# Main_circuit.net
KiCad netlist of a schematic drawn in Altium Designer
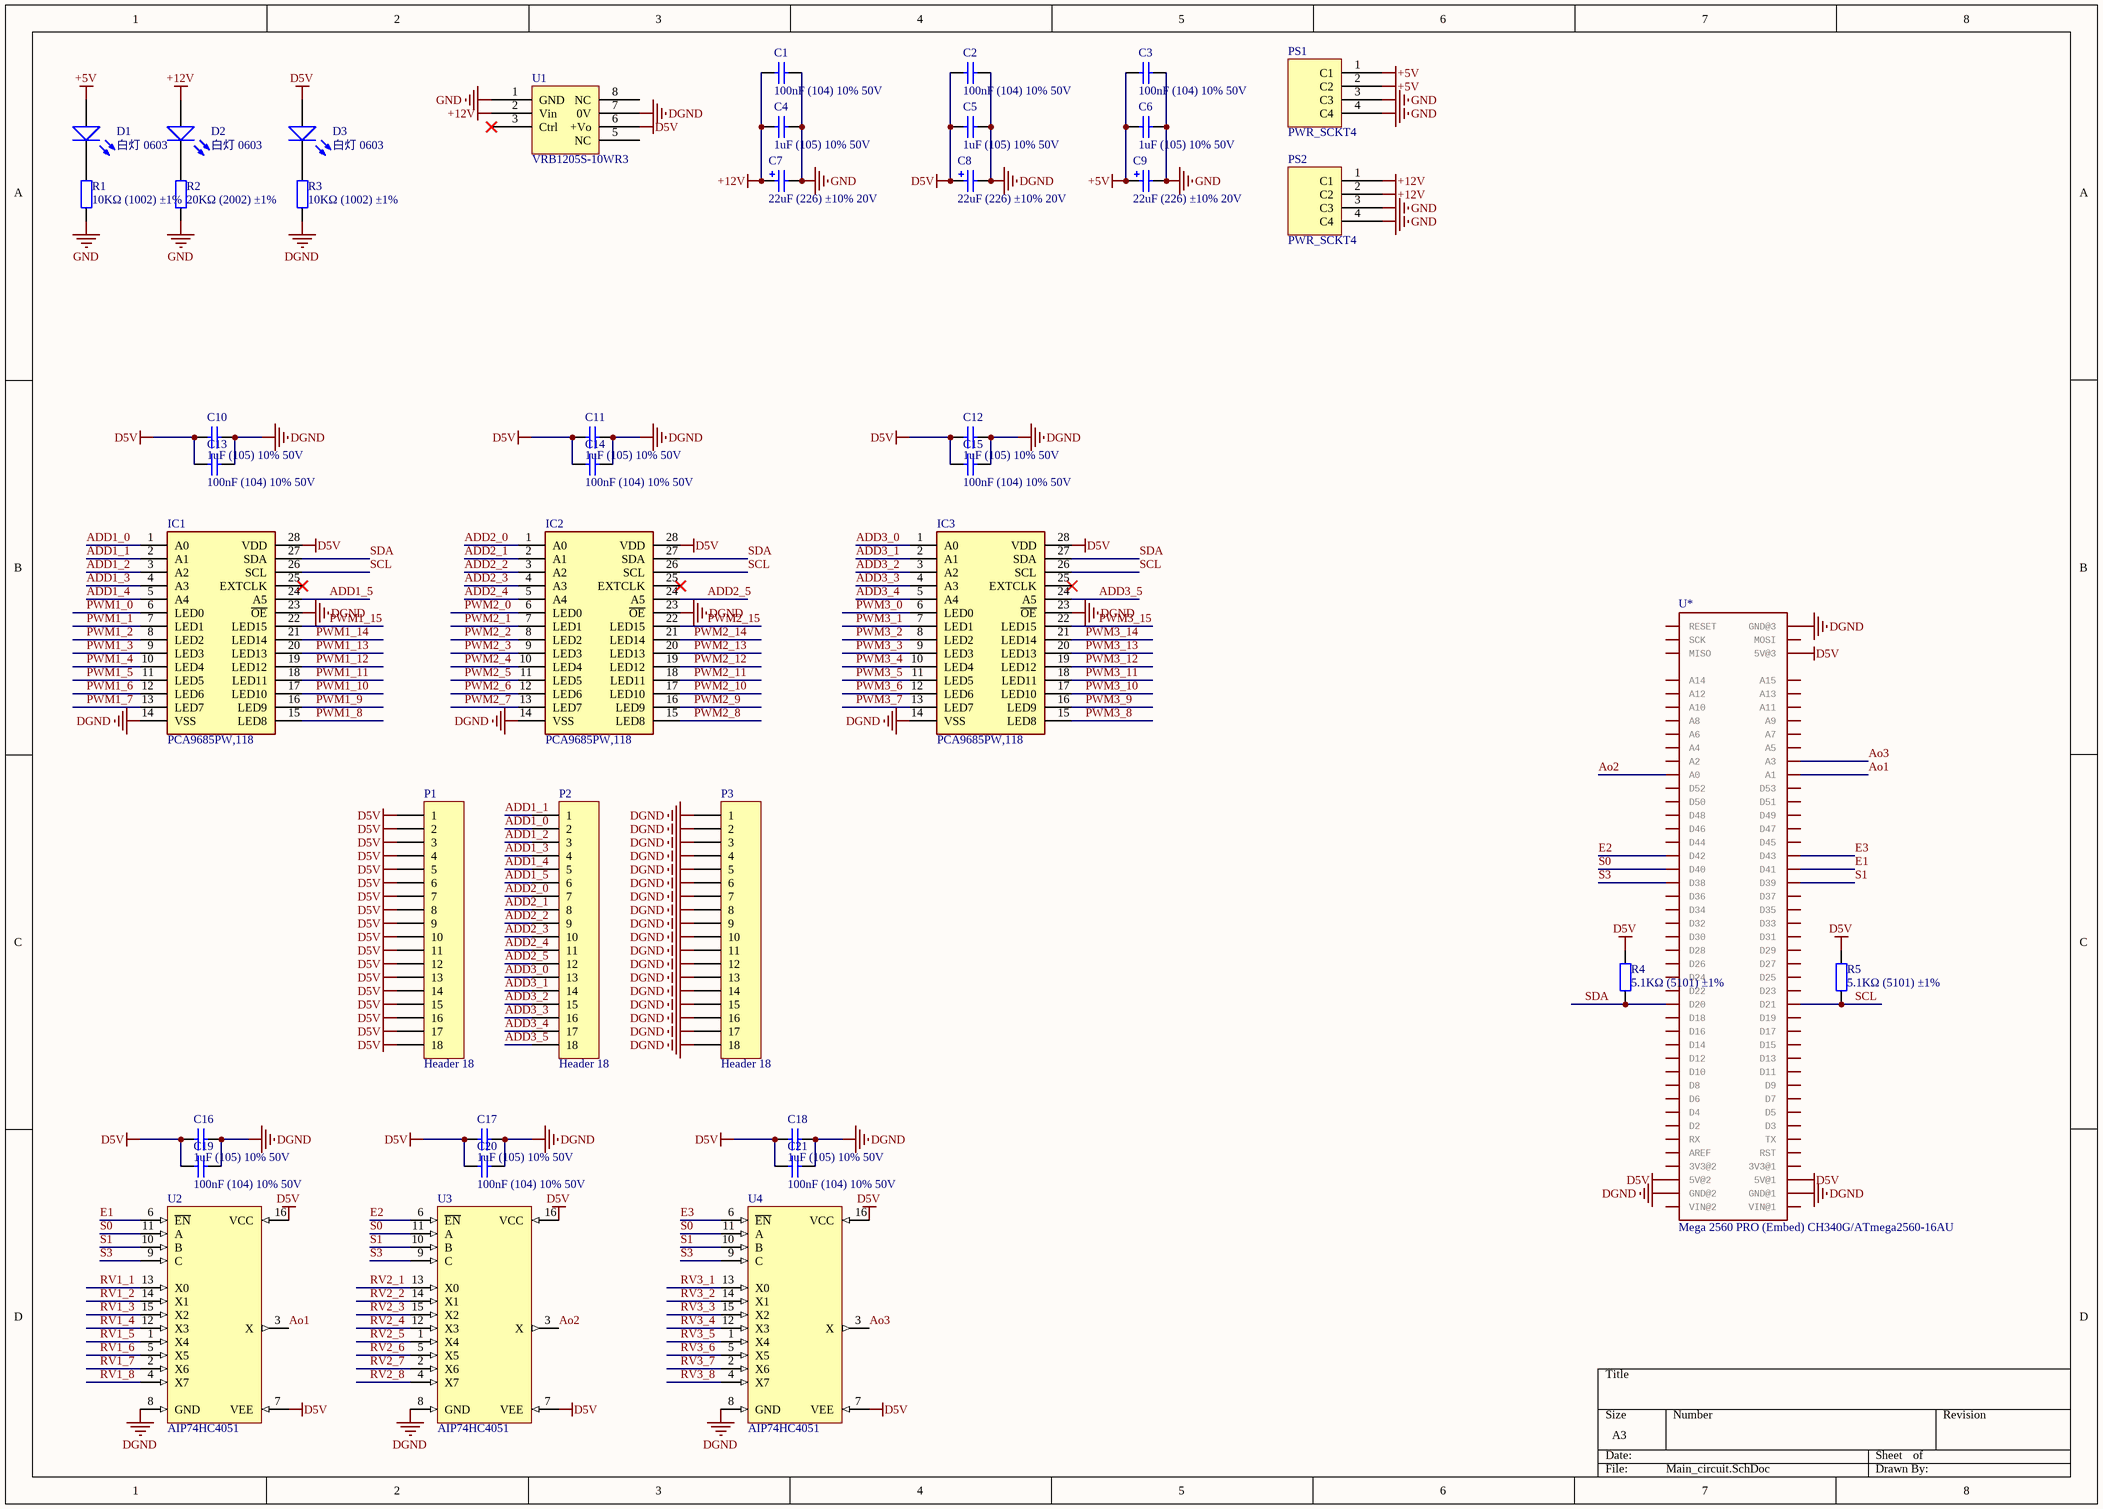
[diagram p0: Main_circuit.SchDoc]

(export (version "E")
  (design (tool "Eeschema 10.0.6"))
  (components
    (comp (ref "C1")
      (value "100nF (104) 10% 50V")
      (footprint "LC-0603_C")
      (description "贴片电容")
      (libsource (lib "Miscellaneous Devices LC") (part "0603 100nF (104) 10% 50V"))
    )
    (comp (ref "C2")
      (value "100nF (104) 10% 50V")
      (footprint "LC-0603_C")
      (description "贴片电容")
      (libsource (lib "Miscellaneous Devices LC") (part "0603 100nF (104) 10% 50V"))
    )
    (comp (ref "C3")
      (value "100nF (104) 10% 50V")
      (footprint "LC-0603_C")
      (description "贴片电容")
      (libsource (lib "Miscellaneous Devices LC") (part "0603 100nF (104) 10% 50V"))
    )
    (comp (ref "C4")
      (value "1uF (105) 10% 50V")
      (footprint "LC-0603_C")
      (description "贴片电容")
      (libsource (lib "Miscellaneous Devices LC") (part "0603 1uF (105) 10% 50V"))
    )
    (comp (ref "C5")
      (value "1uF (105) 10% 50V")
      (footprint "LC-0603_C")
      (description "贴片电容")
      (libsource (lib "Miscellaneous Devices LC") (part "0603 1uF (105) 10% 50V"))
    )
    (comp (ref "C6")
      (value "1uF (105) 10% 50V")
      (footprint "LC-0603_C")
      (description "贴片电容")
      (libsource (lib "Miscellaneous Devices LC") (part "0603 1uF (105) 10% 50V"))
    )
    (comp (ref "C7")
      (value "22uF (226) ±10% 20V")
      (footprint "LC-CASE-B_3528")
      (description "钽电容")
      (libsource (lib "Miscellaneous Devices LC") (part "3216 10uF (106) 10% 16V"))
    )
    (comp (ref "C8")
      (value "22uF (226) ±10% 20V")
      (footprint "LC-CASE-B_3528")
      (description "钽电容")
      (libsource (lib "Miscellaneous Devices LC") (part "3216 10uF (106) 10% 16V"))
    )
    (comp (ref "C9")
      (value "22uF (226) ±10% 20V")
      (footprint "LC-CASE-B_3528")
      (description "钽电容")
      (libsource (lib "Miscellaneous Devices LC") (part "3216 10uF (106) 10% 16V"))
    )
    (comp (ref "C10")
      (value "1uF (105) 10% 50V")
      (footprint "LC-0603_C")
      (description "贴片电容")
      (libsource (lib "Miscellaneous Devices LC") (part "0603 1uF (105) 10% 50V"))
    )
    (comp (ref "C11")
      (value "1uF (105) 10% 50V")
      (footprint "LC-0603_C")
      (description "贴片电容")
      (libsource (lib "Miscellaneous Devices LC") (part "0603 1uF (105) 10% 50V"))
    )
    (comp (ref "C12")
      (value "1uF (105) 10% 50V")
      (footprint "LC-0603_C")
      (description "贴片电容")
      (libsource (lib "Miscellaneous Devices LC") (part "0603 1uF (105) 10% 50V"))
    )
    (comp (ref "C13")
      (value "100nF (104) 10% 50V")
      (footprint "LC-0603_C")
      (description "贴片电容")
      (libsource (lib "Miscellaneous Devices LC") (part "0603 100nF (104) 10% 50V"))
    )
    (comp (ref "C14")
      (value "100nF (104) 10% 50V")
      (footprint "LC-0603_C")
      (description "贴片电容")
      (libsource (lib "Miscellaneous Devices LC") (part "0603 100nF (104) 10% 50V"))
    )
    (comp (ref "C15")
      (value "100nF (104) 10% 50V")
      (footprint "LC-0603_C")
      (description "贴片电容")
      (libsource (lib "Miscellaneous Devices LC") (part "0603 100nF (104) 10% 50V"))
    )
    (comp (ref "C16")
      (value "1uF (105) 10% 50V")
      (footprint "LC-0603_C")
      (description "贴片电容")
      (libsource (lib "Miscellaneous Devices LC") (part "0603 1uF (105) 10% 50V"))
    )
    (comp (ref "C17")
      (value "1uF (105) 10% 50V")
      (footprint "LC-0603_C")
      (description "贴片电容")
      (libsource (lib "Miscellaneous Devices LC") (part "0603 1uF (105) 10% 50V"))
    )
    (comp (ref "C18")
      (value "1uF (105) 10% 50V")
      (footprint "LC-0603_C")
      (description "贴片电容")
      (libsource (lib "Miscellaneous Devices LC") (part "0603 1uF (105) 10% 50V"))
    )
    (comp (ref "C19")
      (value "100nF (104) 10% 50V")
      (footprint "LC-0603_C")
      (description "贴片电容")
      (libsource (lib "Miscellaneous Devices LC") (part "0603 100nF (104) 10% 50V"))
    )
    (comp (ref "C20")
      (value "100nF (104) 10% 50V")
      (footprint "LC-0603_C")
      (description "贴片电容")
      (libsource (lib "Miscellaneous Devices LC") (part "0603 100nF (104) 10% 50V"))
    )
    (comp (ref "C21")
      (value "100nF (104) 10% 50V")
      (footprint "LC-0603_C")
      (description "贴片电容")
      (libsource (lib "Miscellaneous Devices LC") (part "0603 100nF (104) 10% 50V"))
    )
    (comp (ref "D1")
      (value "白灯 0603")
      (footprint "LC-0603_LED_S1")
      (description "发光二极管")
      (libsource (lib "Miscellaneous Devices LC") (part "0603 白灯"))
    )
    (comp (ref "D2")
      (value "白灯 0603")
      (footprint "LC-0603_LED_S1")
      (description "发光二极管")
      (libsource (lib "Miscellaneous Devices LC") (part "0603 白灯"))
    )
    (comp (ref "D3")
      (value "白灯 0603")
      (footprint "LC-0603_LED_S1")
      (description "发光二极管")
      (libsource (lib "Miscellaneous Devices LC") (part "0603 白灯"))
    )
    (comp (ref "IC1")
      (value "PCA9685PW,118")
      (footprint "LC-TSSOP-28")
      (description "Integrated Circuit")
      (libsource (lib "*") (part "PCA9685PW,118"))
    )
    (comp (ref "IC2")
      (value "PCA9685PW,118")
      (footprint "LC-TSSOP-28")
      (description "Integrated Circuit")
      (libsource (lib "*") (part "PCA9685PW,118"))
    )
    (comp (ref "IC3")
      (value "PCA9685PW,118")
      (footprint "LC-TSSOP-28")
      (description "Integrated Circuit")
      (libsource (lib "*") (part "PCA9685PW,118"))
    )
    (comp (ref "P1")
      (value "Header 18")
      (footprint "HDR1X18")
      (description "Header, 18-Pin")
      (fields (field (name "PUBLISHER") "Altium Limited"))
      (libsource (lib "Miscellaneous Connectors") (part "Header 18"))
    )
    (comp (ref "P2")
      (value "Header 18")
      (footprint "HDR1X18")
      (description "Header, 18-Pin")
      (fields (field (name "PUBLISHER") "Altium Limited"))
      (libsource (lib "Miscellaneous Connectors") (part "Header 18"))
    )
    (comp (ref "P3")
      (value "Header 18")
      (footprint "HDR1X18")
      (description "Header, 18-Pin")
      (fields (field (name "PUBLISHER") "Altium Limited"))
      (libsource (lib "Miscellaneous Connectors") (part "Header 18"))
    )
    (comp (ref "PS1")
      (value "PWR_SCKT4")
      (footprint "PWR_SCKT_4P3.81")
      (description "POWER SOCKET")
      (libsource (lib "PG_lib") (part "POWER_SOCKET4"))
    )
    (comp (ref "PS2")
      (value "PWR_SCKT4")
      (footprint "PWR_SCKT_4P3.81")
      (description "POWER SOCKET")
      (libsource (lib "PG_lib") (part "POWER_SOCKET4"))
    )
    (comp (ref "R1")
      (value "10KΩ (1002) ±1%")
      (footprint "LC-0603_R")
      (description "贴片电阻")
      (libsource (lib "Miscellaneous Devices LC") (part "0603 10KΩ (1002) 1%"))
    )
    (comp (ref "R2")
      (value "20KΩ (2002) ±1%")
      (footprint "LC-0603_R")
      (description "贴片电阻")
      (libsource (lib "Miscellaneous Devices LC") (part "0603 20KΩ (2002) 1%"))
    )
    (comp (ref "R3")
      (value "10KΩ (1002) ±1%")
      (footprint "LC-0603_R")
      (description "贴片电阻")
      (libsource (lib "Miscellaneous Devices LC") (part "0603 10KΩ (1002) 1%"))
    )
    (comp (ref "R4")
      (value "5.1KΩ (5101) ±1%")
      (footprint "LC-0603_R")
      (description "贴片电阻")
      (libsource (lib "Miscellaneous Devices LC") (part "0603 5.1KΩ (5101) 1%"))
    )
    (comp (ref "R5")
      (value "5.1KΩ (5101) ±1%")
      (footprint "LC-0603_R")
      (description "贴片电阻")
      (libsource (lib "Miscellaneous Devices LC") (part "0603 5.1KΩ (5101) 1%"))
    )
    (comp (ref "U*")
      (value "Mega 2560 PRO (Embed) CH340G/ATmega2560-16AU")
      (footprint "Mega 2560 PRO (Embed)")
      (libsource (lib "Mega2560Pro") (part "Mega 2560 PRO (Embed)"))
    )
    (comp (ref "U1")
      (value "VRB1205S-10WR3")
      (footprint "VRB1205S-10WR3")
      (libsource (lib "Schlib1") (part "VRB1205S-10WR3"))
    )
    (comp (ref "U2")
      (value "AIP74HC4051")
      (footprint "LC-SOP-16_150mil")
      (description "4000系列逻辑芯片")
      (libsource (lib "Miscellaneous Devices LC") (part "CD4051BM96"))
    )
    (comp (ref "U3")
      (value "AIP74HC4051")
      (footprint "LC-SOP-16_150mil")
      (description "4000系列逻辑芯片")
      (libsource (lib "Miscellaneous Devices LC") (part "CD4051BM96"))
    )
    (comp (ref "U4")
      (value "AIP74HC4051")
      (footprint "LC-SOP-16_150mil")
      (description "4000系列逻辑芯片")
      (libsource (lib "Miscellaneous Devices LC") (part "CD4051BM96"))
    )
  )
  (nets
    (net (code "1") (name "+5V") (class "Default")
      (node (ref "C3") (pin "2") (pinfunction "2_2") (pintype "passive"))
      (node (ref "C6") (pin "2") (pinfunction "2_2") (pintype "passive"))
      (node (ref "C9") (pin "1") (pinfunction "1_1") (pintype "passive"))
      (node (ref "D1") (pin "A") (pinfunction "A_A") (pintype "passive"))
      (node (ref "PS1") (pin "1") (pinfunction "C1_1") (pintype "passive"))
      (node (ref "PS1") (pin "2") (pinfunction "C2_2") (pintype "passive"))
    )
    (net (code "2") (name "+12V") (class "Default")
      (node (ref "C1") (pin "2") (pinfunction "2_2") (pintype "passive"))
      (node (ref "C4") (pin "2") (pinfunction "2_2") (pintype "passive"))
      (node (ref "C7") (pin "1") (pinfunction "1_1") (pintype "passive"))
      (node (ref "D2") (pin "A") (pinfunction "A_A") (pintype "passive"))
      (node (ref "PS2") (pin "1") (pinfunction "C1_1") (pintype "passive"))
      (node (ref "PS2") (pin "2") (pinfunction "C2_2") (pintype "passive"))
      (node (ref "U1") (pin "2") (pinfunction "Vin_2") (pintype "passive"))
    )
    (net (code "3") (name "/ADD1_0") (class "Default")
      (node (ref "IC1") (pin "1") (pinfunction "A0_1") (pintype "passive"))
      (node (ref "P2") (pin "2") (pinfunction "2_2") (pintype "passive"))
    )
    (net (code "4") (name "/ADD1_1") (class "Default")
      (node (ref "IC1") (pin "2") (pinfunction "A1_2") (pintype "passive"))
      (node (ref "P2") (pin "1") (pinfunction "1_1") (pintype "passive"))
    )
    (net (code "5") (name "/ADD1_2") (class "Default")
      (node (ref "IC1") (pin "3") (pinfunction "A2_3") (pintype "passive"))
      (node (ref "P2") (pin "3") (pinfunction "3_3") (pintype "passive"))
    )
    (net (code "6") (name "/ADD1_3") (class "Default")
      (node (ref "IC1") (pin "4") (pinfunction "A3_4") (pintype "passive"))
      (node (ref "P2") (pin "4") (pinfunction "4_4") (pintype "passive"))
    )
    (net (code "7") (name "/ADD1_4") (class "Default")
      (node (ref "IC1") (pin "5") (pinfunction "A4_5") (pintype "passive"))
      (node (ref "P2") (pin "5") (pinfunction "5_5") (pintype "passive"))
    )
    (net (code "8") (name "/ADD1_5") (class "Default")
      (node (ref "IC1") (pin "24") (pinfunction "A5_24") (pintype "passive"))
      (node (ref "P2") (pin "6") (pinfunction "6_6") (pintype "passive"))
    )
    (net (code "9") (name "/ADD2_0") (class "Default")
      (node (ref "IC2") (pin "1") (pinfunction "A0_1") (pintype "passive"))
      (node (ref "P2") (pin "7") (pinfunction "7_7") (pintype "passive"))
    )
    (net (code "10") (name "/ADD2_1") (class "Default")
      (node (ref "IC2") (pin "2") (pinfunction "A1_2") (pintype "passive"))
      (node (ref "P2") (pin "8") (pinfunction "8_8") (pintype "passive"))
    )
    (net (code "11") (name "/ADD2_2") (class "Default")
      (node (ref "IC2") (pin "3") (pinfunction "A2_3") (pintype "passive"))
      (node (ref "P2") (pin "9") (pinfunction "9_9") (pintype "passive"))
    )
    (net (code "12") (name "/ADD2_3") (class "Default")
      (node (ref "IC2") (pin "4") (pinfunction "A3_4") (pintype "passive"))
      (node (ref "P2") (pin "10") (pinfunction "10_10") (pintype "passive"))
    )
    (net (code "13") (name "/ADD2_4") (class "Default")
      (node (ref "IC2") (pin "5") (pinfunction "A4_5") (pintype "passive"))
      (node (ref "P2") (pin "11") (pinfunction "11_11") (pintype "passive"))
    )
    (net (code "14") (name "/ADD2_5") (class "Default")
      (node (ref "IC2") (pin "24") (pinfunction "A5_24") (pintype "passive"))
      (node (ref "P2") (pin "12") (pinfunction "12_12") (pintype "passive"))
    )
    (net (code "15") (name "/ADD3_0") (class "Default")
      (node (ref "IC3") (pin "1") (pinfunction "A0_1") (pintype "passive"))
      (node (ref "P2") (pin "13") (pinfunction "13_13") (pintype "passive"))
    )
    (net (code "16") (name "/ADD3_1") (class "Default")
      (node (ref "IC3") (pin "2") (pinfunction "A1_2") (pintype "passive"))
      (node (ref "P2") (pin "14") (pinfunction "14_14") (pintype "passive"))
    )
    (net (code "17") (name "/ADD3_2") (class "Default")
      (node (ref "IC3") (pin "3") (pinfunction "A2_3") (pintype "passive"))
      (node (ref "P2") (pin "15") (pinfunction "15_15") (pintype "passive"))
    )
    (net (code "18") (name "/ADD3_3") (class "Default")
      (node (ref "IC3") (pin "4") (pinfunction "A3_4") (pintype "passive"))
      (node (ref "P2") (pin "16") (pinfunction "16_16") (pintype "passive"))
    )
    (net (code "19") (name "/ADD3_4") (class "Default")
      (node (ref "IC3") (pin "5") (pinfunction "A4_5") (pintype "passive"))
      (node (ref "P2") (pin "17") (pinfunction "17_17") (pintype "passive"))
    )
    (net (code "20") (name "/ADD3_5") (class "Default")
      (node (ref "IC3") (pin "24") (pinfunction "A5_24") (pintype "passive"))
      (node (ref "P2") (pin "18") (pinfunction "18_18") (pintype "passive"))
    )
    (net (code "21") (name "/Ao1") (class "Default")
      (node (ref "U*") (pin "A1") (pinfunction "A1_A1") (pintype "bidirectional"))
      (node (ref "U2") (pin "3") (pinfunction "X_3") (pintype "output"))
    )
    (net (code "22") (name "/Ao2") (class "Default")
      (node (ref "U*") (pin "A0") (pinfunction "A0_A0") (pintype "bidirectional"))
      (node (ref "U3") (pin "3") (pinfunction "X_3") (pintype "output"))
    )
    (net (code "23") (name "/Ao3") (class "Default")
      (node (ref "U*") (pin "A3") (pinfunction "A3_A3") (pintype "bidirectional"))
      (node (ref "U4") (pin "3") (pinfunction "X_3") (pintype "output"))
    )
    (net (code "24") (name "/E1") (class "Default")
      (node (ref "U*") (pin "D41") (pinfunction "D41_D41") (pintype "bidirectional"))
      (node (ref "U2") (pin "6") (pinfunction "~{EN}_6") (pintype "input"))
    )
    (net (code "25") (name "/E2") (class "Default")
      (node (ref "U*") (pin "D42") (pinfunction "D42_D42") (pintype "bidirectional"))
      (node (ref "U3") (pin "6") (pinfunction "~{EN}_6") (pintype "input"))
    )
    (net (code "26") (name "/E3") (class "Default")
      (node (ref "U*") (pin "D43") (pinfunction "D43_D43") (pintype "bidirectional"))
      (node (ref "U4") (pin "6") (pinfunction "~{EN}_6") (pintype "input"))
    )
    (net (code "27") (name "/PWM1_0") (class "Default")
      (node (ref "IC1") (pin "6") (pinfunction "LED0_6") (pintype "passive"))
    )
    (net (code "28") (name "/PWM1_1") (class "Default")
      (node (ref "IC1") (pin "7") (pinfunction "LED1_7") (pintype "passive"))
    )
    (net (code "29") (name "/PWM1_2") (class "Default")
      (node (ref "IC1") (pin "8") (pinfunction "LED2_8") (pintype "passive"))
    )
    (net (code "30") (name "/PWM1_3") (class "Default")
      (node (ref "IC1") (pin "9") (pinfunction "LED3_9") (pintype "passive"))
    )
    (net (code "31") (name "/PWM1_4") (class "Default")
      (node (ref "IC1") (pin "10") (pinfunction "LED4_10") (pintype "passive"))
    )
    (net (code "32") (name "/PWM1_5") (class "Default")
      (node (ref "IC1") (pin "11") (pinfunction "LED5_11") (pintype "passive"))
    )
    (net (code "33") (name "/PWM1_6") (class "Default")
      (node (ref "IC1") (pin "12") (pinfunction "LED6_12") (pintype "passive"))
    )
    (net (code "34") (name "/PWM1_7") (class "Default")
      (node (ref "IC1") (pin "13") (pinfunction "LED7_13") (pintype "passive"))
    )
    (net (code "35") (name "/PWM1_8") (class "Default")
      (node (ref "IC1") (pin "15") (pinfunction "LED8_15") (pintype "passive"))
    )
    (net (code "36") (name "/PWM1_9") (class "Default")
      (node (ref "IC1") (pin "16") (pinfunction "LED9_16") (pintype "passive"))
    )
    (net (code "37") (name "/PWM1_10") (class "Default")
      (node (ref "IC1") (pin "17") (pinfunction "LED10_17") (pintype "passive"))
    )
    (net (code "38") (name "/PWM1_11") (class "Default")
      (node (ref "IC1") (pin "18") (pinfunction "LED11_18") (pintype "passive"))
    )
    (net (code "39") (name "/PWM1_12") (class "Default")
      (node (ref "IC1") (pin "19") (pinfunction "LED12_19") (pintype "passive"))
    )
    (net (code "40") (name "/PWM1_13") (class "Default")
      (node (ref "IC1") (pin "20") (pinfunction "LED13_20") (pintype "passive"))
    )
    (net (code "41") (name "/PWM1_14") (class "Default")
      (node (ref "IC1") (pin "21") (pinfunction "LED14_21") (pintype "passive"))
    )
    (net (code "42") (name "/PWM1_15") (class "Default")
      (node (ref "IC1") (pin "22") (pinfunction "LED15_22") (pintype "passive"))
    )
    (net (code "43") (name "/PWM2_0") (class "Default")
      (node (ref "IC2") (pin "6") (pinfunction "LED0_6") (pintype "passive"))
    )
    (net (code "44") (name "/PWM2_1") (class "Default")
      (node (ref "IC2") (pin "7") (pinfunction "LED1_7") (pintype "passive"))
    )
    (net (code "45") (name "/PWM2_2") (class "Default")
      (node (ref "IC2") (pin "8") (pinfunction "LED2_8") (pintype "passive"))
    )
    (net (code "46") (name "/PWM2_3") (class "Default")
      (node (ref "IC2") (pin "9") (pinfunction "LED3_9") (pintype "passive"))
    )
    (net (code "47") (name "/PWM2_4") (class "Default")
      (node (ref "IC2") (pin "10") (pinfunction "LED4_10") (pintype "passive"))
    )
    (net (code "48") (name "/PWM2_5") (class "Default")
      (node (ref "IC2") (pin "11") (pinfunction "LED5_11") (pintype "passive"))
    )
    (net (code "49") (name "/PWM2_6") (class "Default")
      (node (ref "IC2") (pin "12") (pinfunction "LED6_12") (pintype "passive"))
    )
    (net (code "50") (name "/PWM2_7") (class "Default")
      (node (ref "IC2") (pin "13") (pinfunction "LED7_13") (pintype "passive"))
    )
    (net (code "51") (name "/PWM2_8") (class "Default")
      (node (ref "IC2") (pin "15") (pinfunction "LED8_15") (pintype "passive"))
    )
    (net (code "52") (name "/PWM2_9") (class "Default")
      (node (ref "IC2") (pin "16") (pinfunction "LED9_16") (pintype "passive"))
    )
    (net (code "53") (name "/PWM2_10") (class "Default")
      (node (ref "IC2") (pin "17") (pinfunction "LED10_17") (pintype "passive"))
    )
    (net (code "54") (name "/PWM2_11") (class "Default")
      (node (ref "IC2") (pin "18") (pinfunction "LED11_18") (pintype "passive"))
    )
    (net (code "55") (name "/PWM2_12") (class "Default")
      (node (ref "IC2") (pin "19") (pinfunction "LED12_19") (pintype "passive"))
    )
    (net (code "56") (name "/PWM2_13") (class "Default")
      (node (ref "IC2") (pin "20") (pinfunction "LED13_20") (pintype "passive"))
    )
    (net (code "57") (name "/PWM2_14") (class "Default")
      (node (ref "IC2") (pin "21") (pinfunction "LED14_21") (pintype "passive"))
    )
    (net (code "58") (name "/PWM2_15") (class "Default")
      (node (ref "IC2") (pin "22") (pinfunction "LED15_22") (pintype "passive"))
    )
    (net (code "59") (name "/PWM3_0") (class "Default")
      (node (ref "IC3") (pin "6") (pinfunction "LED0_6") (pintype "passive"))
    )
    (net (code "60") (name "/PWM3_1") (class "Default")
      (node (ref "IC3") (pin "7") (pinfunction "LED1_7") (pintype "passive"))
    )
    (net (code "61") (name "/PWM3_2") (class "Default")
      (node (ref "IC3") (pin "8") (pinfunction "LED2_8") (pintype "passive"))
    )
    (net (code "62") (name "/PWM3_3") (class "Default")
      (node (ref "IC3") (pin "9") (pinfunction "LED3_9") (pintype "passive"))
    )
    (net (code "63") (name "/PWM3_4") (class "Default")
      (node (ref "IC3") (pin "10") (pinfunction "LED4_10") (pintype "passive"))
    )
    (net (code "64") (name "/PWM3_5") (class "Default")
      (node (ref "IC3") (pin "11") (pinfunction "LED5_11") (pintype "passive"))
    )
    (net (code "65") (name "/PWM3_6") (class "Default")
      (node (ref "IC3") (pin "12") (pinfunction "LED6_12") (pintype "passive"))
    )
    (net (code "66") (name "/PWM3_7") (class "Default")
      (node (ref "IC3") (pin "13") (pinfunction "LED7_13") (pintype "passive"))
    )
    (net (code "67") (name "/PWM3_8") (class "Default")
      (node (ref "IC3") (pin "15") (pinfunction "LED8_15") (pintype "passive"))
    )
    (net (code "68") (name "/PWM3_9") (class "Default")
      (node (ref "IC3") (pin "16") (pinfunction "LED9_16") (pintype "passive"))
    )
    (net (code "69") (name "/PWM3_10") (class "Default")
      (node (ref "IC3") (pin "17") (pinfunction "LED10_17") (pintype "passive"))
    )
    (net (code "70") (name "/PWM3_11") (class "Default")
      (node (ref "IC3") (pin "18") (pinfunction "LED11_18") (pintype "passive"))
    )
    (net (code "71") (name "/PWM3_12") (class "Default")
      (node (ref "IC3") (pin "19") (pinfunction "LED12_19") (pintype "passive"))
    )
    (net (code "72") (name "/PWM3_13") (class "Default")
      (node (ref "IC3") (pin "20") (pinfunction "LED13_20") (pintype "passive"))
    )
    (net (code "73") (name "/PWM3_14") (class "Default")
      (node (ref "IC3") (pin "21") (pinfunction "LED14_21") (pintype "passive"))
    )
    (net (code "74") (name "/PWM3_15") (class "Default")
      (node (ref "IC3") (pin "22") (pinfunction "LED15_22") (pintype "passive"))
    )
    (net (code "75") (name "/RV1_1") (class "Default")
      (node (ref "U2") (pin "13") (pinfunction "X0_13") (pintype "input"))
    )
    (net (code "76") (name "/RV1_2") (class "Default")
      (node (ref "U2") (pin "14") (pinfunction "X1_14") (pintype "input"))
    )
    (net (code "77") (name "/RV1_3") (class "Default")
      (node (ref "U2") (pin "15") (pinfunction "X2_15") (pintype "input"))
    )
    (net (code "78") (name "/RV1_4") (class "Default")
      (node (ref "U2") (pin "12") (pinfunction "X3_12") (pintype "input"))
    )
    (net (code "79") (name "/RV1_5") (class "Default")
      (node (ref "U2") (pin "1") (pinfunction "X4_1") (pintype "input"))
    )
    (net (code "80") (name "/RV1_6") (class "Default")
      (node (ref "U2") (pin "5") (pinfunction "X5_5") (pintype "input"))
    )
    (net (code "81") (name "/RV1_7") (class "Default")
      (node (ref "U2") (pin "2") (pinfunction "X6_2") (pintype "input"))
    )
    (net (code "82") (name "/RV1_8") (class "Default")
      (node (ref "U2") (pin "4") (pinfunction "X7_4") (pintype "input"))
    )
    (net (code "83") (name "/RV2_1") (class "Default")
      (node (ref "U3") (pin "13") (pinfunction "X0_13") (pintype "input"))
    )
    (net (code "84") (name "/RV2_2") (class "Default")
      (node (ref "U3") (pin "14") (pinfunction "X1_14") (pintype "input"))
    )
    (net (code "85") (name "/RV2_3") (class "Default")
      (node (ref "U3") (pin "15") (pinfunction "X2_15") (pintype "input"))
    )
    (net (code "86") (name "/RV2_4") (class "Default")
      (node (ref "U3") (pin "12") (pinfunction "X3_12") (pintype "input"))
    )
    (net (code "87") (name "/RV2_5") (class "Default")
      (node (ref "U3") (pin "1") (pinfunction "X4_1") (pintype "input"))
    )
    (net (code "88") (name "/RV2_6") (class "Default")
      (node (ref "U3") (pin "5") (pinfunction "X5_5") (pintype "input"))
    )
    (net (code "89") (name "/RV2_7") (class "Default")
      (node (ref "U3") (pin "2") (pinfunction "X6_2") (pintype "input"))
    )
    (net (code "90") (name "/RV2_8") (class "Default")
      (node (ref "U3") (pin "4") (pinfunction "X7_4") (pintype "input"))
    )
    (net (code "91") (name "/RV3_1") (class "Default")
      (node (ref "U4") (pin "13") (pinfunction "X0_13") (pintype "input"))
    )
    (net (code "92") (name "/RV3_2") (class "Default")
      (node (ref "U4") (pin "14") (pinfunction "X1_14") (pintype "input"))
    )
    (net (code "93") (name "/RV3_3") (class "Default")
      (node (ref "U4") (pin "15") (pinfunction "X2_15") (pintype "input"))
    )
    (net (code "94") (name "/RV3_4") (class "Default")
      (node (ref "U4") (pin "12") (pinfunction "X3_12") (pintype "input"))
    )
    (net (code "95") (name "/RV3_5") (class "Default")
      (node (ref "U4") (pin "1") (pinfunction "X4_1") (pintype "input"))
    )
    (net (code "96") (name "/RV3_6") (class "Default")
      (node (ref "U4") (pin "5") (pinfunction "X5_5") (pintype "input"))
    )
    (net (code "97") (name "/RV3_7") (class "Default")
      (node (ref "U4") (pin "2") (pinfunction "X6_2") (pintype "input"))
    )
    (net (code "98") (name "/RV3_8") (class "Default")
      (node (ref "U4") (pin "4") (pinfunction "X7_4") (pintype "input"))
    )
    (net (code "99") (name "/S0") (class "Default")
      (node (ref "U*") (pin "D40") (pinfunction "D40_D40") (pintype "bidirectional"))
      (node (ref "U2") (pin "11") (pinfunction "A_11") (pintype "input"))
      (node (ref "U3") (pin "11") (pinfunction "A_11") (pintype "input"))
      (node (ref "U4") (pin "11") (pinfunction "A_11") (pintype "input"))
    )
    (net (code "100") (name "/S1") (class "Default")
      (node (ref "U*") (pin "D39") (pinfunction "D39_D39") (pintype "bidirectional"))
      (node (ref "U2") (pin "10") (pinfunction "B_10") (pintype "input"))
      (node (ref "U3") (pin "10") (pinfunction "B_10") (pintype "input"))
      (node (ref "U4") (pin "10") (pinfunction "B_10") (pintype "input"))
    )
    (net (code "101") (name "/S3") (class "Default")
      (node (ref "U*") (pin "D38") (pinfunction "D38_D38") (pintype "bidirectional"))
      (node (ref "U2") (pin "9") (pinfunction "C_9") (pintype "input"))
      (node (ref "U3") (pin "9") (pinfunction "C_9") (pintype "input"))
      (node (ref "U4") (pin "9") (pinfunction "C_9") (pintype "input"))
    )
    (net (code "102") (name "/SCL") (class "Default")
      (node (ref "IC1") (pin "26") (pinfunction "SCL_26") (pintype "passive"))
      (node (ref "IC2") (pin "26") (pinfunction "SCL_26") (pintype "passive"))
      (node (ref "IC3") (pin "26") (pinfunction "SCL_26") (pintype "passive"))
      (node (ref "R5") (pin "1") (pinfunction "1_1") (pintype "passive"))
      (node (ref "U*") (pin "D21") (pinfunction "D21_D21") (pintype "bidirectional"))
    )
    (net (code "103") (name "/SDA") (class "Default")
      (node (ref "IC1") (pin "27") (pinfunction "SDA_27") (pintype "passive"))
      (node (ref "IC2") (pin "27") (pinfunction "SDA_27") (pintype "passive"))
      (node (ref "IC3") (pin "27") (pinfunction "SDA_27") (pintype "passive"))
      (node (ref "R4") (pin "1") (pinfunction "1_1") (pintype "passive"))
      (node (ref "U*") (pin "D20") (pinfunction "D20_D20") (pintype "bidirectional"))
    )
    (net (code "104") (name "D5V") (class "Default")
      (node (ref "C10") (pin "1") (pinfunction "1_1") (pintype "passive"))
      (node (ref "C11") (pin "1") (pinfunction "1_1") (pintype "passive"))
      (node (ref "C12") (pin "1") (pinfunction "1_1") (pintype "passive"))
      (node (ref "C13") (pin "1") (pinfunction "1_1") (pintype "passive"))
      (node (ref "C14") (pin "1") (pinfunction "1_1") (pintype "passive"))
      (node (ref "C15") (pin "1") (pinfunction "1_1") (pintype "passive"))
      (node (ref "C16") (pin "1") (pinfunction "1_1") (pintype "passive"))
      (node (ref "C17") (pin "1") (pinfunction "1_1") (pintype "passive"))
      (node (ref "C18") (pin "1") (pinfunction "1_1") (pintype "passive"))
      (node (ref "C19") (pin "1") (pinfunction "1_1") (pintype "passive"))
      (node (ref "C2") (pin "2") (pinfunction "2_2") (pintype "passive"))
      (node (ref "C20") (pin "1") (pinfunction "1_1") (pintype "passive"))
      (node (ref "C21") (pin "1") (pinfunction "1_1") (pintype "passive"))
      (node (ref "C5") (pin "2") (pinfunction "2_2") (pintype "passive"))
      (node (ref "C8") (pin "1") (pinfunction "1_1") (pintype "passive"))
      (node (ref "D3") (pin "A") (pinfunction "A_A") (pintype "passive"))
      (node (ref "IC1") (pin "28") (pinfunction "VDD_28") (pintype "passive"))
      (node (ref "IC2") (pin "28") (pinfunction "VDD_28") (pintype "passive"))
      (node (ref "IC3") (pin "28") (pinfunction "VDD_28") (pintype "passive"))
      (node (ref "P1") (pin "1") (pinfunction "1_1") (pintype "passive"))
      (node (ref "P1") (pin "10") (pinfunction "10_10") (pintype "passive"))
      (node (ref "P1") (pin "11") (pinfunction "11_11") (pintype "passive"))
      (node (ref "P1") (pin "12") (pinfunction "12_12") (pintype "passive"))
      (node (ref "P1") (pin "13") (pinfunction "13_13") (pintype "passive"))
      (node (ref "P1") (pin "14") (pinfunction "14_14") (pintype "passive"))
      (node (ref "P1") (pin "15") (pinfunction "15_15") (pintype "passive"))
      (node (ref "P1") (pin "16") (pinfunction "16_16") (pintype "passive"))
      (node (ref "P1") (pin "17") (pinfunction "17_17") (pintype "passive"))
      (node (ref "P1") (pin "18") (pinfunction "18_18") (pintype "passive"))
      (node (ref "P1") (pin "2") (pinfunction "2_2") (pintype "passive"))
      (node (ref "P1") (pin "3") (pinfunction "3_3") (pintype "passive"))
      (node (ref "P1") (pin "4") (pinfunction "4_4") (pintype "passive"))
      (node (ref "P1") (pin "5") (pinfunction "5_5") (pintype "passive"))
      (node (ref "P1") (pin "6") (pinfunction "6_6") (pintype "passive"))
      (node (ref "P1") (pin "7") (pinfunction "7_7") (pintype "passive"))
      (node (ref "P1") (pin "8") (pinfunction "8_8") (pintype "passive"))
      (node (ref "P1") (pin "9") (pinfunction "9_9") (pintype "passive"))
      (node (ref "R4") (pin "2") (pinfunction "2_2") (pintype "passive"))
      (node (ref "R5") (pin "2") (pinfunction "2_2") (pintype "passive"))
      (node (ref "U*") (pin "5V@1") (pinfunction "5V@1_5V@1") (pintype "bidirectional"))
      (node (ref "U*") (pin "5V@2") (pinfunction "5V@2_5V@2") (pintype "bidirectional"))
      (node (ref "U*") (pin "5V@3") (pinfunction "5V@3_5V@3") (pintype "bidirectional"))
      (node (ref "U1") (pin "6") (pinfunction "+Vo_6") (pintype "passive"))
      (node (ref "U2") (pin "16") (pinfunction "VCC_16") (pintype "input"))
      (node (ref "U2") (pin "7") (pinfunction "VEE_7") (pintype "input"))
      (node (ref "U3") (pin "16") (pinfunction "VCC_16") (pintype "input"))
      (node (ref "U3") (pin "7") (pinfunction "VEE_7") (pintype "input"))
      (node (ref "U4") (pin "16") (pinfunction "VCC_16") (pintype "input"))
      (node (ref "U4") (pin "7") (pinfunction "VEE_7") (pintype "input"))
    )
    (net (code "105") (name "DGND") (class "Default")
      (node (ref "C10") (pin "2") (pinfunction "2_2") (pintype "passive"))
      (node (ref "C11") (pin "2") (pinfunction "2_2") (pintype "passive"))
      (node (ref "C12") (pin "2") (pinfunction "2_2") (pintype "passive"))
      (node (ref "C13") (pin "2") (pinfunction "2_2") (pintype "passive"))
      (node (ref "C14") (pin "2") (pinfunction "2_2") (pintype "passive"))
      (node (ref "C15") (pin "2") (pinfunction "2_2") (pintype "passive"))
      (node (ref "C16") (pin "2") (pinfunction "2_2") (pintype "passive"))
      (node (ref "C17") (pin "2") (pinfunction "2_2") (pintype "passive"))
      (node (ref "C18") (pin "2") (pinfunction "2_2") (pintype "passive"))
      (node (ref "C19") (pin "2") (pinfunction "2_2") (pintype "passive"))
      (node (ref "C2") (pin "1") (pinfunction "1_1") (pintype "passive"))
      (node (ref "C20") (pin "2") (pinfunction "2_2") (pintype "passive"))
      (node (ref "C21") (pin "2") (pinfunction "2_2") (pintype "passive"))
      (node (ref "C5") (pin "1") (pinfunction "1_1") (pintype "passive"))
      (node (ref "C8") (pin "2") (pinfunction "2_2") (pintype "passive"))
      (node (ref "IC1") (pin "14") (pinfunction "VSS_14") (pintype "passive"))
      (node (ref "IC1") (pin "23") (pinfunction "~{OE}_23") (pintype "passive"))
      (node (ref "IC2") (pin "14") (pinfunction "VSS_14") (pintype "passive"))
      (node (ref "IC2") (pin "23") (pinfunction "~{OE}_23") (pintype "passive"))
      (node (ref "IC3") (pin "14") (pinfunction "VSS_14") (pintype "passive"))
      (node (ref "IC3") (pin "23") (pinfunction "~{OE}_23") (pintype "passive"))
      (node (ref "P3") (pin "1") (pinfunction "1_1") (pintype "passive"))
      (node (ref "P3") (pin "10") (pinfunction "10_10") (pintype "passive"))
      (node (ref "P3") (pin "11") (pinfunction "11_11") (pintype "passive"))
      (node (ref "P3") (pin "12") (pinfunction "12_12") (pintype "passive"))
      (node (ref "P3") (pin "13") (pinfunction "13_13") (pintype "passive"))
      (node (ref "P3") (pin "14") (pinfunction "14_14") (pintype "passive"))
      (node (ref "P3") (pin "15") (pinfunction "15_15") (pintype "passive"))
      (node (ref "P3") (pin "16") (pinfunction "16_16") (pintype "passive"))
      (node (ref "P3") (pin "17") (pinfunction "17_17") (pintype "passive"))
      (node (ref "P3") (pin "18") (pinfunction "18_18") (pintype "passive"))
      (node (ref "P3") (pin "2") (pinfunction "2_2") (pintype "passive"))
      (node (ref "P3") (pin "3") (pinfunction "3_3") (pintype "passive"))
      (node (ref "P3") (pin "4") (pinfunction "4_4") (pintype "passive"))
      (node (ref "P3") (pin "5") (pinfunction "5_5") (pintype "passive"))
      (node (ref "P3") (pin "6") (pinfunction "6_6") (pintype "passive"))
      (node (ref "P3") (pin "7") (pinfunction "7_7") (pintype "passive"))
      (node (ref "P3") (pin "8") (pinfunction "8_8") (pintype "passive"))
      (node (ref "P3") (pin "9") (pinfunction "9_9") (pintype "passive"))
      (node (ref "R3") (pin "1") (pinfunction "1_1") (pintype "passive"))
      (node (ref "U*") (pin "GND@1") (pinfunction "GND@1_GND@1") (pintype "bidirectional"))
      (node (ref "U*") (pin "GND@2") (pinfunction "GND@2_GND@2") (pintype "bidirectional"))
      (node (ref "U*") (pin "GND@3") (pinfunction "GND@3_GND@3") (pintype "bidirectional"))
      (node (ref "U1") (pin "7") (pinfunction "0V_7") (pintype "passive"))
      (node (ref "U2") (pin "8") (pinfunction "GND_8") (pintype "input"))
      (node (ref "U3") (pin "8") (pinfunction "GND_8") (pintype "input"))
      (node (ref "U4") (pin "8") (pinfunction "GND_8") (pintype "input"))
    )
    (net (code "106") (name "GND") (class "Default")
      (node (ref "C1") (pin "1") (pinfunction "1_1") (pintype "passive"))
      (node (ref "C3") (pin "1") (pinfunction "1_1") (pintype "passive"))
      (node (ref "C4") (pin "1") (pinfunction "1_1") (pintype "passive"))
      (node (ref "C6") (pin "1") (pinfunction "1_1") (pintype "passive"))
      (node (ref "C7") (pin "2") (pinfunction "2_2") (pintype "passive"))
      (node (ref "C9") (pin "2") (pinfunction "2_2") (pintype "passive"))
      (node (ref "PS1") (pin "3") (pinfunction "C3_3") (pintype "passive"))
      (node (ref "PS1") (pin "4") (pinfunction "C4_4") (pintype "passive"))
      (node (ref "PS2") (pin "3") (pinfunction "C3_3") (pintype "passive"))
      (node (ref "PS2") (pin "4") (pinfunction "C4_4") (pintype "passive"))
      (node (ref "R1") (pin "1") (pinfunction "1_1") (pintype "passive"))
      (node (ref "R2") (pin "1") (pinfunction "1_1") (pintype "passive"))
      (node (ref "U1") (pin "1") (pinfunction "GND_1") (pintype "passive"))
    )
    (net (code "107") (name "Net-(D1-PadK)") (class "Default")
      (node (ref "D1") (pin "K") (pinfunction "K_K") (pintype "passive"))
      (node (ref "R1") (pin "2") (pinfunction "2_2") (pintype "passive"))
    )
    (net (code "108") (name "Net-(D2-PadK)") (class "Default")
      (node (ref "D2") (pin "K") (pinfunction "K_K") (pintype "passive"))
      (node (ref "R2") (pin "2") (pinfunction "2_2") (pintype "passive"))
    )
    (net (code "109") (name "Net-(D3-PadK)") (class "Default")
      (node (ref "D3") (pin "K") (pinfunction "K_K") (pintype "passive"))
      (node (ref "R3") (pin "2") (pinfunction "2_2") (pintype "passive"))
    )
    (net (code "110") (name "unconnected-(IC1-EXTCLK-Pad25)") (class "Default")
      (node (ref "IC1") (pin "25") (pinfunction "EXTCLK_25") (pintype "passive+no_connect"))
    )
    (net (code "111") (name "unconnected-(IC2-EXTCLK-Pad25)") (class "Default")
      (node (ref "IC2") (pin "25") (pinfunction "EXTCLK_25") (pintype "passive+no_connect"))
    )
    (net (code "112") (name "unconnected-(IC3-EXTCLK-Pad25)") (class "Default")
      (node (ref "IC3") (pin "25") (pinfunction "EXTCLK_25") (pintype "passive+no_connect"))
    )
    (net (code "113") (name "unconnected-(U*-Pad3V3@1)") (class "Default")
      (node (ref "U*") (pin "3V3@1") (pinfunction "3V3@1_3V3@1") (pintype "bidirectional"))
    )
    (net (code "114") (name "unconnected-(U*-Pad3V3@2)") (class "Default")
      (node (ref "U*") (pin "3V3@2") (pinfunction "3V3@2_3V3@2") (pintype "bidirectional"))
    )
    (net (code "115") (name "unconnected-(U*-PadA2)") (class "Default")
      (node (ref "U*") (pin "A2") (pinfunction "A2_A2") (pintype "bidirectional"))
    )
    (net (code "116") (name "unconnected-(U*-PadA4)") (class "Default")
      (node (ref "U*") (pin "A4") (pinfunction "A4_A4") (pintype "bidirectional"))
    )
    (net (code "117") (name "unconnected-(U*-PadA5)") (class "Default")
      (node (ref "U*") (pin "A5") (pinfunction "A5_A5") (pintype "bidirectional"))
    )
    (net (code "118") (name "unconnected-(U*-PadA6)") (class "Default")
      (node (ref "U*") (pin "A6") (pinfunction "A6_A6") (pintype "bidirectional"))
    )
    (net (code "119") (name "unconnected-(U*-PadA7)") (class "Default")
      (node (ref "U*") (pin "A7") (pinfunction "A7_A7") (pintype "bidirectional"))
    )
    (net (code "120") (name "unconnected-(U*-PadA8)") (class "Default")
      (node (ref "U*") (pin "A8") (pinfunction "A8_A8") (pintype "bidirectional"))
    )
    (net (code "121") (name "unconnected-(U*-PadA9)") (class "Default")
      (node (ref "U*") (pin "A9") (pinfunction "A9_A9") (pintype "bidirectional"))
    )
    (net (code "122") (name "unconnected-(U*-PadA10)") (class "Default")
      (node (ref "U*") (pin "A10") (pinfunction "A10_A10") (pintype "bidirectional"))
    )
    (net (code "123") (name "unconnected-(U*-PadA11)") (class "Default")
      (node (ref "U*") (pin "A11") (pinfunction "A11_A11") (pintype "bidirectional"))
    )
    (net (code "124") (name "unconnected-(U*-PadA12)") (class "Default")
      (node (ref "U*") (pin "A12") (pinfunction "A12_A12") (pintype "bidirectional"))
    )
    (net (code "125") (name "unconnected-(U*-PadA13)") (class "Default")
      (node (ref "U*") (pin "A13") (pinfunction "A13_A13") (pintype "bidirectional"))
    )
    (net (code "126") (name "unconnected-(U*-PadA14)") (class "Default")
      (node (ref "U*") (pin "A14") (pinfunction "A14_A14") (pintype "bidirectional"))
    )
    (net (code "127") (name "unconnected-(U*-PadA15)") (class "Default")
      (node (ref "U*") (pin "A15") (pinfunction "A15_A15") (pintype "bidirectional"))
    )
    (net (code "128") (name "unconnected-(U*-PadAREF)") (class "Default")
      (node (ref "U*") (pin "AREF") (pinfunction "AREF_AREF") (pintype "bidirectional"))
    )
    (net (code "129") (name "unconnected-(U*-PadD2)") (class "Default")
      (node (ref "U*") (pin "D2") (pinfunction "D2_D2") (pintype "bidirectional"))
    )
    (net (code "130") (name "unconnected-(U*-PadD3)") (class "Default")
      (node (ref "U*") (pin "D3") (pinfunction "D3_D3") (pintype "bidirectional"))
    )
    (net (code "131") (name "unconnected-(U*-PadD4)") (class "Default")
      (node (ref "U*") (pin "D4") (pinfunction "D4_D4") (pintype "bidirectional"))
    )
    (net (code "132") (name "unconnected-(U*-PadD5)") (class "Default")
      (node (ref "U*") (pin "D5") (pinfunction "D5_D5") (pintype "bidirectional"))
    )
    (net (code "133") (name "unconnected-(U*-PadD6)") (class "Default")
      (node (ref "U*") (pin "D6") (pinfunction "D6_D6") (pintype "bidirectional"))
    )
    (net (code "134") (name "unconnected-(U*-PadD7)") (class "Default")
      (node (ref "U*") (pin "D7") (pinfunction "D7_D7") (pintype "bidirectional"))
    )
    (net (code "135") (name "unconnected-(U*-PadD8)") (class "Default")
      (node (ref "U*") (pin "D8") (pinfunction "D8_D8") (pintype "bidirectional"))
    )
    (net (code "136") (name "unconnected-(U*-PadD9)") (class "Default")
      (node (ref "U*") (pin "D9") (pinfunction "D9_D9") (pintype "bidirectional"))
    )
    (net (code "137") (name "unconnected-(U*-PadD10)") (class "Default")
      (node (ref "U*") (pin "D10") (pinfunction "D10_D10") (pintype "bidirectional"))
    )
    (net (code "138") (name "unconnected-(U*-PadD11)") (class "Default")
      (node (ref "U*") (pin "D11") (pinfunction "D11_D11") (pintype "bidirectional"))
    )
    (net (code "139") (name "unconnected-(U*-PadD12)") (class "Default")
      (node (ref "U*") (pin "D12") (pinfunction "D12_D12") (pintype "bidirectional"))
    )
    (net (code "140") (name "unconnected-(U*-PadD13)") (class "Default")
      (node (ref "U*") (pin "D13") (pinfunction "D13_D13") (pintype "bidirectional"))
    )
    (net (code "141") (name "unconnected-(U*-PadD14)") (class "Default")
      (node (ref "U*") (pin "D14") (pinfunction "D14_D14") (pintype "bidirectional"))
    )
    (net (code "142") (name "unconnected-(U*-PadD15)") (class "Default")
      (node (ref "U*") (pin "D15") (pinfunction "D15_D15") (pintype "bidirectional"))
    )
    (net (code "143") (name "unconnected-(U*-PadD16)") (class "Default")
      (node (ref "U*") (pin "D16") (pinfunction "D16_D16") (pintype "bidirectional"))
    )
    (net (code "144") (name "unconnected-(U*-PadD17)") (class "Default")
      (node (ref "U*") (pin "D17") (pinfunction "D17_D17") (pintype "bidirectional"))
    )
    (net (code "145") (name "unconnected-(U*-PadD18)") (class "Default")
      (node (ref "U*") (pin "D18") (pinfunction "D18_D18") (pintype "bidirectional"))
    )
    (net (code "146") (name "unconnected-(U*-PadD19)") (class "Default")
      (node (ref "U*") (pin "D19") (pinfunction "D19_D19") (pintype "bidirectional"))
    )
    (net (code "147") (name "unconnected-(U*-PadD22)") (class "Default")
      (node (ref "U*") (pin "D22") (pinfunction "D22_D22") (pintype "bidirectional"))
    )
    (net (code "148") (name "unconnected-(U*-PadD23)") (class "Default")
      (node (ref "U*") (pin "D23") (pinfunction "D23_D23") (pintype "bidirectional"))
    )
    (net (code "149") (name "unconnected-(U*-PadD24)") (class "Default")
      (node (ref "U*") (pin "D24") (pinfunction "D24_D24") (pintype "bidirectional"))
    )
    (net (code "150") (name "unconnected-(U*-PadD25)") (class "Default")
      (node (ref "U*") (pin "D25") (pinfunction "D25_D25") (pintype "bidirectional"))
    )
    (net (code "151") (name "unconnected-(U*-PadD26)") (class "Default")
      (node (ref "U*") (pin "D26") (pinfunction "D26_D26") (pintype "bidirectional"))
    )
    (net (code "152") (name "unconnected-(U*-PadD27)") (class "Default")
      (node (ref "U*") (pin "D27") (pinfunction "D27_D27") (pintype "bidirectional"))
    )
    (net (code "153") (name "unconnected-(U*-PadD28)") (class "Default")
      (node (ref "U*") (pin "D28") (pinfunction "D28_D28") (pintype "bidirectional"))
    )
    (net (code "154") (name "unconnected-(U*-PadD29)") (class "Default")
      (node (ref "U*") (pin "D29") (pinfunction "D29_D29") (pintype "bidirectional"))
    )
    (net (code "155") (name "unconnected-(U*-PadD30)") (class "Default")
      (node (ref "U*") (pin "D30") (pinfunction "D30_D30") (pintype "bidirectional"))
    )
    (net (code "156") (name "unconnected-(U*-PadD31)") (class "Default")
      (node (ref "U*") (pin "D31") (pinfunction "D31_D31") (pintype "bidirectional"))
    )
    (net (code "157") (name "unconnected-(U*-PadD32)") (class "Default")
      (node (ref "U*") (pin "D32") (pinfunction "D32_D32") (pintype "bidirectional"))
    )
    (net (code "158") (name "unconnected-(U*-PadD33)") (class "Default")
      (node (ref "U*") (pin "D33") (pinfunction "D33_D33") (pintype "bidirectional"))
    )
    (net (code "159") (name "unconnected-(U*-PadD34)") (class "Default")
      (node (ref "U*") (pin "D34") (pinfunction "D34_D34") (pintype "bidirectional"))
    )
    (net (code "160") (name "unconnected-(U*-PadD35)") (class "Default")
      (node (ref "U*") (pin "D35") (pinfunction "D35_D35") (pintype "bidirectional"))
    )
    (net (code "161") (name "unconnected-(U*-PadD36)") (class "Default")
      (node (ref "U*") (pin "D36") (pinfunction "D36_D36") (pintype "bidirectional"))
    )
    (net (code "162") (name "unconnected-(U*-PadD37)") (class "Default")
      (node (ref "U*") (pin "D37") (pinfunction "D37_D37") (pintype "bidirectional"))
    )
    (net (code "163") (name "unconnected-(U*-PadD44)") (class "Default")
      (node (ref "U*") (pin "D44") (pinfunction "D44_D44") (pintype "bidirectional"))
    )
    (net (code "164") (name "unconnected-(U*-PadD45)") (class "Default")
      (node (ref "U*") (pin "D45") (pinfunction "D45_D45") (pintype "bidirectional"))
    )
    (net (code "165") (name "unconnected-(U*-PadD46)") (class "Default")
      (node (ref "U*") (pin "D46") (pinfunction "D46_D46") (pintype "bidirectional"))
    )
    (net (code "166") (name "unconnected-(U*-PadD47)") (class "Default")
      (node (ref "U*") (pin "D47") (pinfunction "D47_D47") (pintype "bidirectional"))
    )
    (net (code "167") (name "unconnected-(U*-PadD48)") (class "Default")
      (node (ref "U*") (pin "D48") (pinfunction "D48_D48") (pintype "bidirectional"))
    )
    (net (code "168") (name "unconnected-(U*-PadD49)") (class "Default")
      (node (ref "U*") (pin "D49") (pinfunction "D49_D49") (pintype "bidirectional"))
    )
    (net (code "169") (name "unconnected-(U*-PadD50)") (class "Default")
      (node (ref "U*") (pin "D50") (pinfunction "D50_D50") (pintype "bidirectional"))
    )
    (net (code "170") (name "unconnected-(U*-PadD51)") (class "Default")
      (node (ref "U*") (pin "D51") (pinfunction "D51_D51") (pintype "bidirectional"))
    )
    (net (code "171") (name "unconnected-(U*-PadD52)") (class "Default")
      (node (ref "U*") (pin "D52") (pinfunction "D52_D52") (pintype "bidirectional"))
    )
    (net (code "172") (name "unconnected-(U*-PadD53)") (class "Default")
      (node (ref "U*") (pin "D53") (pinfunction "D53_D53") (pintype "bidirectional"))
    )
    (net (code "173") (name "unconnected-(U*-PadMISO)") (class "Default")
      (node (ref "U*") (pin "MISO") (pinfunction "MISO_MISO") (pintype "bidirectional"))
    )
    (net (code "174") (name "unconnected-(U*-PadMOSI)") (class "Default")
      (node (ref "U*") (pin "MOSI") (pinfunction "MOSI_MOSI") (pintype "bidirectional"))
    )
    (net (code "175") (name "unconnected-(U*-PadRESET)") (class "Default")
      (node (ref "U*") (pin "RESET") (pinfunction "RESET_RESET") (pintype "bidirectional"))
    )
    (net (code "176") (name "unconnected-(U*-PadRST)") (class "Default")
      (node (ref "U*") (pin "RST") (pinfunction "RST_RST") (pintype "bidirectional"))
    )
    (net (code "177") (name "unconnected-(U*-PadRX)") (class "Default")
      (node (ref "U*") (pin "RX") (pinfunction "RX_RX") (pintype "bidirectional"))
    )
    (net (code "178") (name "unconnected-(U*-PadSCK)") (class "Default")
      (node (ref "U*") (pin "SCK") (pinfunction "SCK_SCK") (pintype "bidirectional"))
    )
    (net (code "179") (name "unconnected-(U*-PadTX)") (class "Default")
      (node (ref "U*") (pin "TX") (pinfunction "TX_TX") (pintype "bidirectional"))
    )
    (net (code "180") (name "unconnected-(U*-PadVIN@1)") (class "Default")
      (node (ref "U*") (pin "VIN@1") (pinfunction "VIN@1_VIN@1") (pintype "bidirectional"))
    )
    (net (code "181") (name "unconnected-(U*-PadVIN@2)") (class "Default")
      (node (ref "U*") (pin "VIN@2") (pinfunction "VIN@2_VIN@2") (pintype "bidirectional"))
    )
    (net (code "182") (name "unconnected-(U1-Ctrl-Pad3)") (class "Default")
      (node (ref "U1") (pin "3") (pinfunction "Ctrl_3") (pintype "passive+no_connect"))
    )
    (net (code "183") (name "unconnected-(U1-NC-Pad5)") (class "Default")
      (node (ref "U1") (pin "5") (pinfunction "NC_5") (pintype "passive"))
    )
    (net (code "184") (name "unconnected-(U1-NC-Pad8)") (class "Default")
      (node (ref "U1") (pin "8") (pinfunction "NC_8") (pintype "passive"))
    )
  )
)
